# joystickClocks.net
KiCad netlist of a schematic drawn in Altium Designer
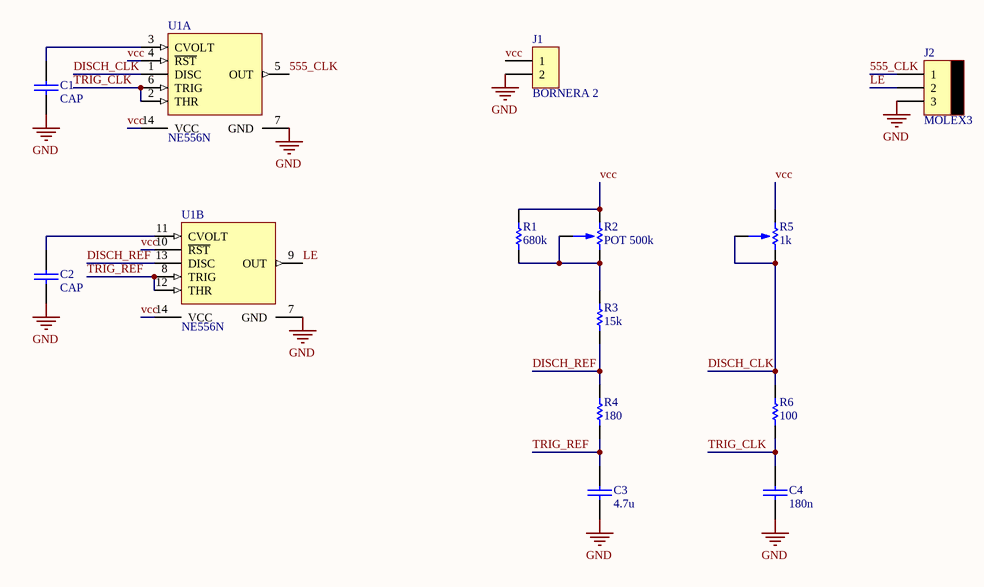
[diagram p0: joystickClocks.SchDoc]

(export (version "E")
  (design (tool "Eeschema 10.0.6"))
  (components
    (comp (ref "C1") (value "CAP") (footprint "0805") (libsource (lib "LIBEBAL") (part "CAP")))
    (comp (ref "C2") (value "CAP") (footprint "0805") (libsource (lib "LIBEBAL") (part "CAP")))
    (comp (ref "C3") (value "4.7u") (footprint "0805") (libsource (lib "LIBEBAL") (part "CAP")))
    (comp (ref "C4") (value "180n") (footprint "0805") (libsource (lib "LIBEBAL") (part "CAP")))
    (comp (ref "J1")
      (value "BORNERA 2")
      (footprint "BORNERA2")
      (libsource (lib "LIBEBAL") (part "BORNERA 2"))
    )
    (comp (ref "J2") (value "MOLEX3") (footprint "MOLEX3") (libsource (lib "LIBEBAL") (part "MOLEX3")))
    (comp (ref "R1") (value "680k") (footprint "0805") (libsource (lib "LIBEBAL") (part "RES")))
    (comp (ref "R2")
      (value "POT 500k")
      (footprint "POTENCIOMETRO")
      (libsource (lib "LIBEBAL") (part "POTENCIOMETRO"))
    )
    (comp (ref "R3") (value "15k") (footprint "0805") (libsource (lib "LIBEBAL") (part "RES")))
    (comp (ref "R4") (value "180") (footprint "RES400") (libsource (lib "LIBEBAL") (part "RES")))
    (comp (ref "R5") (value "1k") (footprint "PRESET V") (libsource (lib "LIBEBAL") (part "PRESET")))
    (comp (ref "R6") (value "100") (footprint "0805") (libsource (lib "LIBEBAL") (part "RES")))
    (comp (ref "U1")
      (value "NE556N")
      (footprint "N014")
      (description "Dual Precision Timer")
      (fields (field (name "PUBLISHER") "Altium Limited"))
      (libsource (lib "TI Analog Timer Circuit") (part "NE556N"))
    )
  )
  (nets
    (net (code "1") (name "/555_CLK") (class "Default")
      (node (ref "J2") (pin "1") (pinfunction "1_1") (pintype "passive"))
      (node (ref "U1") (pin "5") (pinfunction "OUT_5") (pintype "output"))
    )
    (net (code "2") (name "/DISCH_CLK") (class "Default")
      (node (ref "R5") (pin "1") (pinfunction "1_1") (pintype "passive"))
      (node (ref "R5") (pin "2") (pinfunction "2_2") (pintype "passive"))
      (node (ref "R6") (pin "2") (pinfunction "2_2") (pintype "passive"))
      (node (ref "U1") (pin "1") (pinfunction "DISC_1") (pintype "open_collector"))
    )
    (net (code "3") (name "/DISCH_REF") (class "Default")
      (node (ref "R3") (pin "1") (pinfunction "1_1") (pintype "passive"))
      (node (ref "R4") (pin "2") (pinfunction "2_2") (pintype "passive"))
      (node (ref "U1") (pin "13") (pinfunction "DISC_13") (pintype "open_collector"))
    )
    (net (code "4") (name "/LE") (class "Default")
      (node (ref "J2") (pin "2") (pinfunction "2_2") (pintype "passive"))
      (node (ref "U1") (pin "9") (pinfunction "OUT_9") (pintype "output"))
    )
    (net (code "5") (name "/TRIG_CLK") (class "Default")
      (node (ref "C4") (pin "1") (pinfunction "1_1") (pintype "passive"))
      (node (ref "R6") (pin "1") (pinfunction "1_1") (pintype "passive"))
      (node (ref "U1") (pin "2") (pinfunction "THR_2") (pintype "input"))
      (node (ref "U1") (pin "6") (pinfunction "TRIG_6") (pintype "input"))
    )
    (net (code "6") (name "/TRIG_REF") (class "Default")
      (node (ref "C3") (pin "1") (pinfunction "1_1") (pintype "passive"))
      (node (ref "R4") (pin "1") (pinfunction "1_1") (pintype "passive"))
      (node (ref "U1") (pin "12") (pinfunction "THR_12") (pintype "input"))
      (node (ref "U1") (pin "8") (pinfunction "TRIG_8") (pintype "input"))
    )
    (net (code "7") (name "/vcc") (class "Default")
      (node (ref "J1") (pin "1") (pinfunction "1_1") (pintype "passive"))
      (node (ref "R1") (pin "2") (pinfunction "2_2") (pintype "passive"))
      (node (ref "R2") (pin "3") (pinfunction "3_3") (pintype "passive"))
      (node (ref "R5") (pin "3") (pinfunction "3_3") (pintype "passive"))
      (node (ref "U1") (pin "10") (pinfunction "~{RST}_10") (pintype "passive"))
      (node (ref "U1") (pin "14") (pinfunction "VCC_14") (pintype "power_in"))
      (node (ref "U1") (pin "4") (pinfunction "~{RST}_4") (pintype "input"))
    )
    (net (code "8") (name "GND") (class "Default")
      (node (ref "C1") (pin "2") (pinfunction "2_2") (pintype "passive"))
      (node (ref "C2") (pin "2") (pinfunction "2_2") (pintype "passive"))
      (node (ref "C3") (pin "2") (pinfunction "2_2") (pintype "passive"))
      (node (ref "C4") (pin "2") (pinfunction "2_2") (pintype "passive"))
      (node (ref "J1") (pin "2") (pinfunction "2_2") (pintype "passive"))
      (node (ref "J2") (pin "3") (pinfunction "3_3") (pintype "passive"))
      (node (ref "U1") (pin "7") (pinfunction "GND_7") (pintype "power_in"))
    )
    (net (code "9") (name "Net-(R1-Pad1)") (class "Default")
      (node (ref "R1") (pin "1") (pinfunction "1_1") (pintype "passive"))
      (node (ref "R2") (pin "1") (pinfunction "1_1") (pintype "passive"))
      (node (ref "R2") (pin "2") (pinfunction "2_2") (pintype "passive"))
      (node (ref "R3") (pin "2") (pinfunction "2_2") (pintype "passive"))
    )
    (net (code "10") (name "Net-(U1A-CVOLT)") (class "Default")
      (node (ref "C1") (pin "1") (pinfunction "1_1") (pintype "passive"))
      (node (ref "U1") (pin "3") (pinfunction "CVOLT_3") (pintype "input"))
    )
    (net (code "11") (name "Net-(U1B-CVOLT)") (class "Default")
      (node (ref "C2") (pin "1") (pinfunction "1_1") (pintype "passive"))
      (node (ref "U1") (pin "11") (pinfunction "CVOLT_11") (pintype "input"))
    )
  )
)
